# 1x9x1_3.net
KiCad netlist of a schematic drawn in Altium Designer
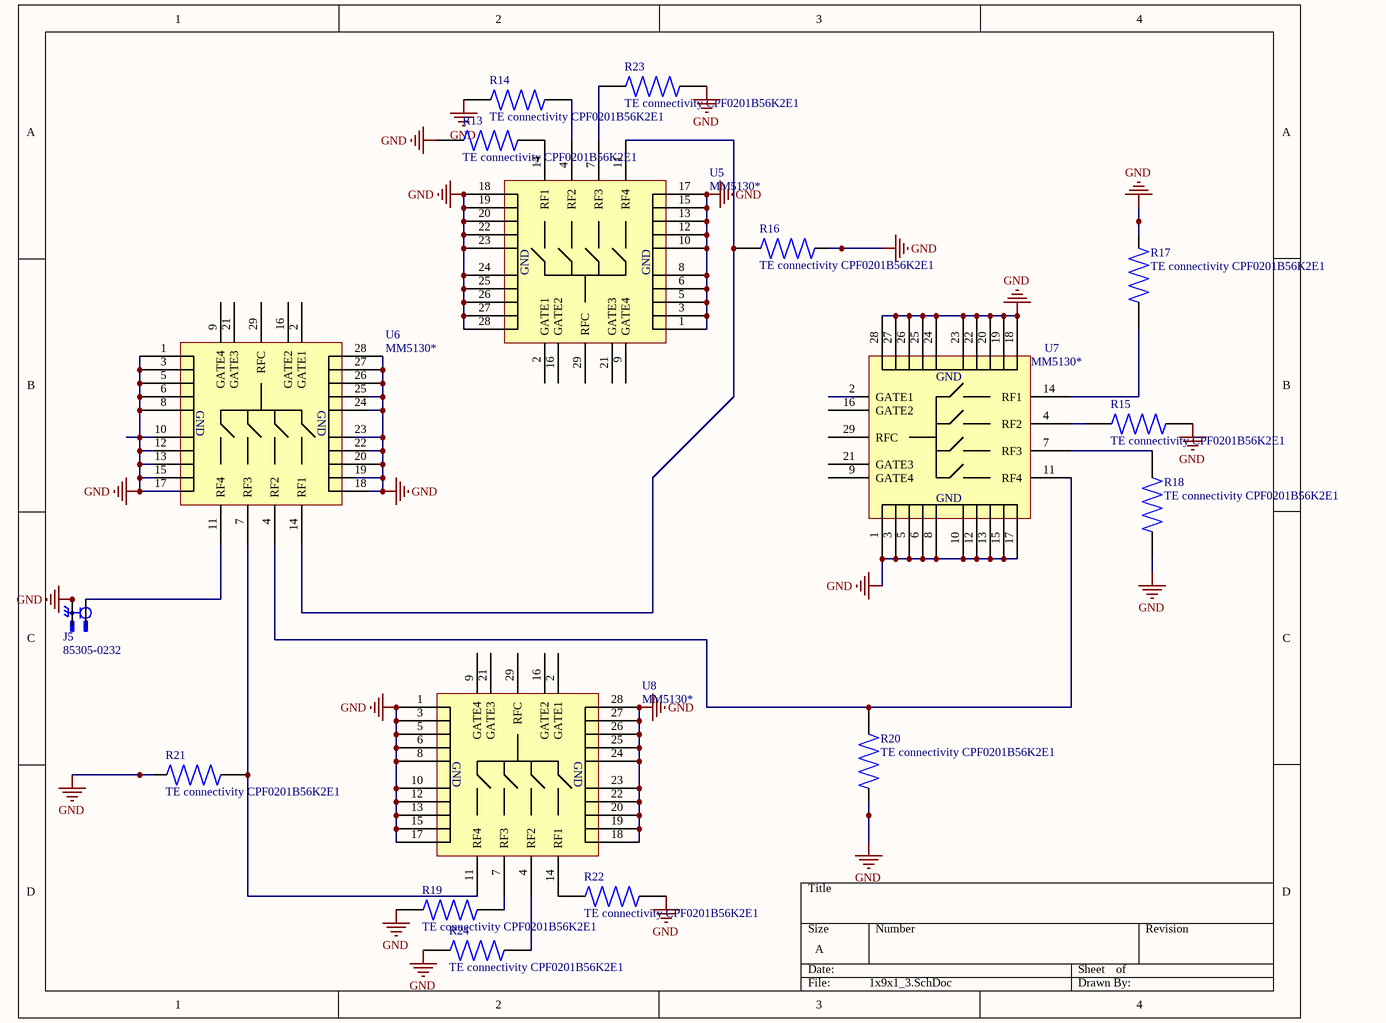
[diagram p0: 1x9x1_3.SchDoc]

(export (version "E")
  (design (tool "Eeschema 10.0.6"))
  (components
    (comp (ref "J5")
      (value "85305-0232")
      (footprint "MOLEX_85305-0232")
      (description "SMP Connector Plug, Male Pin 50Ohm Surface Mount Solder")
      (fields (field (name "MP") "853050232") (field (name "MF") "Molex"))
      (libsource (lib "85305-0232") (part "85305-0232"))
    )
    (comp (ref "R13")
      (value "TE connectivity CPF0201B56K2E1")
      (footprint "0201-resistor")
      (description "CPF 0201 56K2 0.1% 25PPM 1K RL")
      (fields (field (name "MP") "ERJ1GN0R00C") (field (name "MFGR PART NO.") "CPF0201B56K2E1"))
      (libsource (lib "SchlibLafe") (part "TE connectivity CPF0201B56K2E1"))
    )
    (comp (ref "R14")
      (value "TE connectivity CPF0201B56K2E1")
      (footprint "0201-resistor")
      (description "CPF 0201 56K2 0.1% 25PPM 1K RL")
      (fields (field (name "MP") "ERJ1GN0R00C") (field (name "MFGR PART NO.") "CPF0201B56K2E1"))
      (libsource (lib "SchlibLafe") (part "TE connectivity CPF0201B56K2E1"))
    )
    (comp (ref "R15")
      (value "TE connectivity CPF0201B56K2E1")
      (footprint "0201-resistor")
      (description "CPF 0201 56K2 0.1% 25PPM 1K RL")
      (fields (field (name "MP") "ERJ1GN0R00C") (field (name "MFGR PART NO.") "CPF0201B56K2E1"))
      (libsource (lib "SchlibLafe") (part "TE connectivity CPF0201B56K2E1"))
    )
    (comp (ref "R16")
      (value "TE connectivity CPF0201B56K2E1")
      (footprint "0201-resistor")
      (description "CPF 0201 56K2 0.1% 25PPM 1K RL")
      (fields (field (name "MP") "ERJ1GN0R00C") (field (name "MFGR PART NO.") "CPF0201B56K2E1"))
      (libsource (lib "SchlibLafe") (part "TE connectivity CPF0201B56K2E1"))
    )
    (comp (ref "R17")
      (value "TE connectivity CPF0201B56K2E1")
      (footprint "0201-resistor")
      (description "CPF 0201 56K2 0.1% 25PPM 1K RL")
      (fields (field (name "MP") "ERJ1GN0R00C") (field (name "MFGR PART NO.") "CPF0201B56K2E1"))
      (libsource (lib "SchlibLafe") (part "TE connectivity CPF0201B56K2E1"))
    )
    (comp (ref "R18")
      (value "TE connectivity CPF0201B56K2E1")
      (footprint "0201-resistor")
      (description "CPF 0201 56K2 0.1% 25PPM 1K RL")
      (fields (field (name "MP") "ERJ1GN0R00C") (field (name "MFGR PART NO.") "CPF0201B56K2E1"))
      (libsource (lib "SchlibLafe") (part "TE connectivity CPF0201B56K2E1"))
    )
    (comp (ref "R19")
      (value "TE connectivity CPF0201B56K2E1")
      (footprint "0201-resistor")
      (description "CPF 0201 56K2 0.1% 25PPM 1K RL")
      (fields (field (name "MP") "ERJ1GN0R00C") (field (name "MFGR PART NO.") "CPF0201B56K2E1"))
      (libsource (lib "SchlibLafe") (part "TE connectivity CPF0201B56K2E1"))
    )
    (comp (ref "R20")
      (value "TE connectivity CPF0201B56K2E1")
      (footprint "0201-resistor")
      (description "CPF 0201 56K2 0.1% 25PPM 1K RL")
      (fields (field (name "MP") "ERJ1GN0R00C") (field (name "MFGR PART NO.") "CPF0201B56K2E1"))
      (libsource (lib "SchlibLafe") (part "TE connectivity CPF0201B56K2E1"))
    )
    (comp (ref "R21")
      (value "TE connectivity CPF0201B56K2E1")
      (footprint "0201-resistor")
      (description "CPF 0201 56K2 0.1% 25PPM 1K RL")
      (fields (field (name "MP") "ERJ1GN0R00C") (field (name "MFGR PART NO.") "CPF0201B56K2E1"))
      (libsource (lib "SchlibLafe") (part "TE connectivity CPF0201B56K2E1"))
    )
    (comp (ref "R22")
      (value "TE connectivity CPF0201B56K2E1")
      (footprint "0201-resistor")
      (description "CPF 0201 56K2 0.1% 25PPM 1K RL")
      (fields (field (name "MP") "ERJ1GN0R00C") (field (name "MFGR PART NO.") "CPF0201B56K2E1"))
      (libsource (lib "SchlibLafe") (part "TE connectivity CPF0201B56K2E1"))
    )
    (comp (ref "R23")
      (value "TE connectivity CPF0201B56K2E1")
      (footprint "0201-resistor")
      (description "CPF 0201 56K2 0.1% 25PPM 1K RL")
      (fields (field (name "MP") "ERJ1GN0R00C") (field (name "MFGR PART NO.") "CPF0201B56K2E1"))
      (libsource (lib "SchlibLafe") (part "TE connectivity CPF0201B56K2E1"))
    )
    (comp (ref "R24")
      (value "TE connectivity CPF0201B56K2E1")
      (footprint "0201-resistor")
      (description "CPF 0201 56K2 0.1% 25PPM 1K RL")
      (fields (field (name "MP") "ERJ1GN0R00C") (field (name "MFGR PART NO.") "CPF0201B56K2E1"))
      (libsource (lib "SchlibLafe") (part "TE connectivity CPF0201B56K2E1"))
    )
    (comp (ref "U5")
      (value "MM5130*")
      (footprint "MM5130-NORM_PCB_NOFLOOD")
      (description "High power SP4T MEMs switch")
      (libsource (lib "MM5130_SCHSYM") (part "IC-MM5130"))
    )
    (comp (ref "U6")
      (value "MM5130*")
      (footprint "MM5130-NORM_PCB_NOFLOOD")
      (description "High power SP4T MEMs switch")
      (libsource (lib "") (part "IC-MM5130_1"))
    )
    (comp (ref "U7")
      (value "MM5130*")
      (footprint "MM5130-NORM_PCB_NOFLOOD")
      (description "High power SP4T MEMs switch")
      (libsource (lib "") (part "IC-MM5130_2"))
    )
    (comp (ref "U8")
      (value "MM5130*")
      (footprint "MM5130-NORM_PCB_NOFLOOD")
      (description "High power SP4T MEMs switch")
      (libsource (lib "") (part "IC-MM5130_1"))
    )
  )
  (nets
    (net (code "1") (name "GND") (class "Default")
      (node (ref "J5") (pin "10") (pinfunction "2_10") (pintype "passive"))
      (node (ref "J5") (pin "11") (pinfunction "2_11") (pintype "passive"))
      (node (ref "J5") (pin "12") (pinfunction "2_12") (pintype "passive"))
      (node (ref "J5") (pin "13") (pinfunction "2_13") (pintype "passive"))
      (node (ref "J5") (pin "14") (pinfunction "2_14") (pintype "passive"))
      (node (ref "J5") (pin "15") (pinfunction "2_15") (pintype "passive"))
      (node (ref "J5") (pin "16") (pinfunction "2_16") (pintype "passive"))
      (node (ref "J5") (pin "17") (pinfunction "2_17") (pintype "passive"))
      (node (ref "J5") (pin "18") (pinfunction "2_18") (pintype "passive"))
      (node (ref "J5") (pin "2") (pinfunction "2_2") (pintype "passive"))
      (node (ref "J5") (pin "3") (pinfunction "2_3") (pintype "passive"))
      (node (ref "J5") (pin "4") (pinfunction "2_4") (pintype "passive"))
      (node (ref "J5") (pin "5") (pinfunction "2_5") (pintype "passive"))
      (node (ref "J5") (pin "6") (pinfunction "2_6") (pintype "passive"))
      (node (ref "J5") (pin "7") (pinfunction "2_7") (pintype "passive"))
      (node (ref "J5") (pin "8") (pinfunction "2_8") (pintype "passive"))
      (node (ref "J5") (pin "9") (pinfunction "2_9") (pintype "passive"))
      (node (ref "R13") (pin "1") (pinfunction "1_1") (pintype "passive"))
      (node (ref "R14") (pin "2") (pinfunction "2_2") (pintype "passive"))
      (node (ref "R15") (pin "2") (pinfunction "2_2") (pintype "passive"))
      (node (ref "R16") (pin "1") (pinfunction "1_1") (pintype "passive"))
      (node (ref "R17") (pin "1") (pinfunction "1_1") (pintype "passive"))
      (node (ref "R18") (pin "1") (pinfunction "1_1") (pintype "passive"))
      (node (ref "R19") (pin "1") (pinfunction "1_1") (pintype "passive"))
      (node (ref "R20") (pin "2") (pinfunction "2_2") (pintype "passive"))
      (node (ref "R21") (pin "2") (pinfunction "2_2") (pintype "passive"))
      (node (ref "R22") (pin "1") (pinfunction "1_1") (pintype "passive"))
      (node (ref "R23") (pin "1") (pinfunction "1_1") (pintype "passive"))
      (node (ref "R24") (pin "1") (pinfunction "1_1") (pintype "passive"))
      (node (ref "U5") (pin "1") (pinfunction "GND_1") (pintype "passive"))
      (node (ref "U5") (pin "10") (pinfunction "GND_10") (pintype "passive"))
      (node (ref "U5") (pin "12") (pinfunction "GND_12") (pintype "passive"))
      (node (ref "U5") (pin "13") (pinfunction "GND_13") (pintype "passive"))
      (node (ref "U5") (pin "15") (pinfunction "GND_15") (pintype "passive"))
      (node (ref "U5") (pin "17") (pinfunction "GND_17") (pintype "passive"))
      (node (ref "U5") (pin "18") (pinfunction "GND_18") (pintype "passive"))
      (node (ref "U5") (pin "19") (pinfunction "GND_19") (pintype "passive"))
      (node (ref "U5") (pin "20") (pinfunction "GND_20") (pintype "passive"))
      (node (ref "U5") (pin "22") (pinfunction "GND_22") (pintype "passive"))
      (node (ref "U5") (pin "23") (pinfunction "GND_23") (pintype "passive"))
      (node (ref "U5") (pin "24") (pinfunction "GND_24") (pintype "passive"))
      (node (ref "U5") (pin "25") (pinfunction "GND_25") (pintype "passive"))
      (node (ref "U5") (pin "26") (pinfunction "GND_26") (pintype "passive"))
      (node (ref "U5") (pin "27") (pinfunction "GND_27") (pintype "passive"))
      (node (ref "U5") (pin "28") (pinfunction "GND_28") (pintype "passive"))
      (node (ref "U5") (pin "3") (pinfunction "GND_3") (pintype "passive"))
      (node (ref "U5") (pin "5") (pinfunction "GND_5") (pintype "passive"))
      (node (ref "U5") (pin "6") (pinfunction "GND_6") (pintype "passive"))
      (node (ref "U5") (pin "8") (pinfunction "GND_8") (pintype "passive"))
      (node (ref "U6") (pin "1") (pinfunction "GND_1") (pintype "passive"))
      (node (ref "U6") (pin "10") (pinfunction "GND_10") (pintype "passive"))
      (node (ref "U6") (pin "12") (pinfunction "GND_12") (pintype "passive"))
      (node (ref "U6") (pin "13") (pinfunction "GND_13") (pintype "passive"))
      (node (ref "U6") (pin "15") (pinfunction "GND_15") (pintype "passive"))
      (node (ref "U6") (pin "17") (pinfunction "GND_17") (pintype "passive"))
      (node (ref "U6") (pin "18") (pinfunction "GND_18") (pintype "passive"))
      (node (ref "U6") (pin "19") (pinfunction "GND_19") (pintype "passive"))
      (node (ref "U6") (pin "20") (pinfunction "GND_20") (pintype "passive"))
      (node (ref "U6") (pin "22") (pinfunction "GND_22") (pintype "passive"))
      (node (ref "U6") (pin "23") (pinfunction "GND_23") (pintype "passive"))
      (node (ref "U6") (pin "24") (pinfunction "GND_24") (pintype "passive"))
      (node (ref "U6") (pin "25") (pinfunction "GND_25") (pintype "passive"))
      (node (ref "U6") (pin "26") (pinfunction "GND_26") (pintype "passive"))
      (node (ref "U6") (pin "27") (pinfunction "GND_27") (pintype "passive"))
      (node (ref "U6") (pin "28") (pinfunction "GND_28") (pintype "passive"))
      (node (ref "U6") (pin "3") (pinfunction "GND_3") (pintype "passive"))
      (node (ref "U6") (pin "5") (pinfunction "GND_5") (pintype "passive"))
      (node (ref "U6") (pin "6") (pinfunction "GND_6") (pintype "passive"))
      (node (ref "U6") (pin "8") (pinfunction "GND_8") (pintype "passive"))
      (node (ref "U7") (pin "1") (pinfunction "GND_1") (pintype "passive"))
      (node (ref "U7") (pin "10") (pinfunction "GND_10") (pintype "passive"))
      (node (ref "U7") (pin "12") (pinfunction "GND_12") (pintype "passive"))
      (node (ref "U7") (pin "13") (pinfunction "GND_13") (pintype "passive"))
      (node (ref "U7") (pin "15") (pinfunction "GND_15") (pintype "passive"))
      (node (ref "U7") (pin "17") (pinfunction "GND_17") (pintype "passive"))
      (node (ref "U7") (pin "18") (pinfunction "GND_18") (pintype "passive"))
      (node (ref "U7") (pin "19") (pinfunction "GND_19") (pintype "passive"))
      (node (ref "U7") (pin "20") (pinfunction "GND_20") (pintype "passive"))
      (node (ref "U7") (pin "22") (pinfunction "GND_22") (pintype "passive"))
      (node (ref "U7") (pin "23") (pinfunction "GND_23") (pintype "passive"))
      (node (ref "U7") (pin "24") (pinfunction "GND_24") (pintype "passive"))
      (node (ref "U7") (pin "25") (pinfunction "GND_25") (pintype "passive"))
      (node (ref "U7") (pin "26") (pinfunction "GND_26") (pintype "passive"))
      (node (ref "U7") (pin "27") (pinfunction "GND_27") (pintype "passive"))
      (node (ref "U7") (pin "28") (pinfunction "GND_28") (pintype "passive"))
      (node (ref "U7") (pin "3") (pinfunction "GND_3") (pintype "passive"))
      (node (ref "U7") (pin "5") (pinfunction "GND_5") (pintype "passive"))
      (node (ref "U7") (pin "6") (pinfunction "GND_6") (pintype "passive"))
      (node (ref "U7") (pin "8") (pinfunction "GND_8") (pintype "passive"))
      (node (ref "U8") (pin "1") (pinfunction "GND_1") (pintype "passive"))
      (node (ref "U8") (pin "10") (pinfunction "GND_10") (pintype "passive"))
      (node (ref "U8") (pin "12") (pinfunction "GND_12") (pintype "passive"))
      (node (ref "U8") (pin "13") (pinfunction "GND_13") (pintype "passive"))
      (node (ref "U8") (pin "15") (pinfunction "GND_15") (pintype "passive"))
      (node (ref "U8") (pin "17") (pinfunction "GND_17") (pintype "passive"))
      (node (ref "U8") (pin "18") (pinfunction "GND_18") (pintype "passive"))
      (node (ref "U8") (pin "19") (pinfunction "GND_19") (pintype "passive"))
      (node (ref "U8") (pin "20") (pinfunction "GND_20") (pintype "passive"))
      (node (ref "U8") (pin "22") (pinfunction "GND_22") (pintype "passive"))
      (node (ref "U8") (pin "23") (pinfunction "GND_23") (pintype "passive"))
      (node (ref "U8") (pin "24") (pinfunction "GND_24") (pintype "passive"))
      (node (ref "U8") (pin "25") (pinfunction "GND_25") (pintype "passive"))
      (node (ref "U8") (pin "26") (pinfunction "GND_26") (pintype "passive"))
      (node (ref "U8") (pin "27") (pinfunction "GND_27") (pintype "passive"))
      (node (ref "U8") (pin "28") (pinfunction "GND_28") (pintype "passive"))
      (node (ref "U8") (pin "3") (pinfunction "GND_3") (pintype "passive"))
      (node (ref "U8") (pin "5") (pinfunction "GND_5") (pintype "passive"))
      (node (ref "U8") (pin "6") (pinfunction "GND_6") (pintype "passive"))
      (node (ref "U8") (pin "8") (pinfunction "GND_8") (pintype "passive"))
    )
    (net (code "2") (name "Net-(U5-RF1)") (class "Default")
      (node (ref "R13") (pin "2") (pinfunction "2_2") (pintype "passive"))
      (node (ref "U5") (pin "14") (pinfunction "RF1_14") (pintype "passive"))
    )
    (net (code "3") (name "Net-(U5-RF2)") (class "Default")
      (node (ref "R14") (pin "1") (pinfunction "1_1") (pintype "passive"))
      (node (ref "U5") (pin "4") (pinfunction "RF2_4") (pintype "passive"))
    )
    (net (code "4") (name "Net-(U5-RF3)") (class "Default")
      (node (ref "R23") (pin "2") (pinfunction "2_2") (pintype "passive"))
      (node (ref "U5") (pin "7") (pinfunction "RF3_7") (pintype "passive"))
    )
    (net (code "5") (name "Net-(U5-RF4)") (class "Default")
      (node (ref "R16") (pin "2") (pinfunction "2_2") (pintype "passive"))
      (node (ref "U5") (pin "11") (pinfunction "RF4_11") (pintype "passive"))
      (node (ref "U6") (pin "14") (pinfunction "RF1_14") (pintype "passive"))
    )
    (net (code "6") (name "Net-(U6-RF2)") (class "Default")
      (node (ref "R20") (pin "1") (pinfunction "1_1") (pintype "passive"))
      (node (ref "U6") (pin "4") (pinfunction "RF2_4") (pintype "passive"))
      (node (ref "U7") (pin "11") (pinfunction "RF4_11") (pintype "passive"))
    )
    (net (code "7") (name "Net-(U6-RF3)") (class "Default")
      (node (ref "R21") (pin "1") (pinfunction "1_1") (pintype "passive"))
      (node (ref "U6") (pin "7") (pinfunction "RF3_7") (pintype "passive"))
      (node (ref "U8") (pin "11") (pinfunction "RF4_11") (pintype "passive"))
    )
    (net (code "8") (name "Net-(U6-RF4)") (class "Default")
      (node (ref "J5") (pin "1") (pinfunction "1_1") (pintype "passive"))
      (node (ref "U6") (pin "11") (pinfunction "RF4_11") (pintype "passive"))
    )
    (net (code "9") (name "Net-(U7-RF1)") (class "Default")
      (node (ref "R17") (pin "2") (pinfunction "2_2") (pintype "passive"))
      (node (ref "U7") (pin "14") (pinfunction "RF1_14") (pintype "passive"))
    )
    (net (code "10") (name "Net-(U7-RF2)") (class "Default")
      (node (ref "R15") (pin "1") (pinfunction "1_1") (pintype "passive"))
      (node (ref "U7") (pin "4") (pinfunction "RF2_4") (pintype "passive"))
    )
    (net (code "11") (name "Net-(U7-RF3)") (class "Default")
      (node (ref "R18") (pin "2") (pinfunction "2_2") (pintype "passive"))
      (node (ref "U7") (pin "7") (pinfunction "RF3_7") (pintype "passive"))
    )
    (net (code "12") (name "Net-(U8-RF1)") (class "Default")
      (node (ref "R22") (pin "2") (pinfunction "2_2") (pintype "passive"))
      (node (ref "U8") (pin "14") (pinfunction "RF1_14") (pintype "passive"))
    )
    (net (code "13") (name "Net-(U8-RF2)") (class "Default")
      (node (ref "R24") (pin "2") (pinfunction "2_2") (pintype "passive"))
      (node (ref "U8") (pin "4") (pinfunction "RF2_4") (pintype "passive"))
    )
    (net (code "14") (name "Net-(U8-RF3)") (class "Default")
      (node (ref "R19") (pin "2") (pinfunction "2_2") (pintype "passive"))
      (node (ref "U8") (pin "7") (pinfunction "RF3_7") (pintype "passive"))
    )
    (net (code "15") (name "unconnected-(U5-GATE1-Pad2)") (class "Default")
      (node (ref "U5") (pin "2") (pinfunction "GATE1_2") (pintype "passive"))
    )
    (net (code "16") (name "unconnected-(U5-GATE2-Pad16)") (class "Default")
      (node (ref "U5") (pin "16") (pinfunction "GATE2_16") (pintype "passive"))
    )
    (net (code "17") (name "unconnected-(U5-GATE3-Pad21)") (class "Default")
      (node (ref "U5") (pin "21") (pinfunction "GATE3_21") (pintype "passive"))
    )
    (net (code "18") (name "unconnected-(U5-GATE4-Pad9)") (class "Default")
      (node (ref "U5") (pin "9") (pinfunction "GATE4_9") (pintype "passive"))
    )
    (net (code "19") (name "unconnected-(U5-RFC-Pad29)") (class "Default")
      (node (ref "U5") (pin "29") (pinfunction "RFC_29") (pintype "passive"))
    )
    (net (code "20") (name "unconnected-(U6-GATE1-Pad2)") (class "Default")
      (node (ref "U6") (pin "2") (pinfunction "GATE1_2") (pintype "passive"))
    )
    (net (code "21") (name "unconnected-(U6-GATE2-Pad16)") (class "Default")
      (node (ref "U6") (pin "16") (pinfunction "GATE2_16") (pintype "passive"))
    )
    (net (code "22") (name "unconnected-(U6-GATE3-Pad21)") (class "Default")
      (node (ref "U6") (pin "21") (pinfunction "GATE3_21") (pintype "passive"))
    )
    (net (code "23") (name "unconnected-(U6-GATE4-Pad9)") (class "Default")
      (node (ref "U6") (pin "9") (pinfunction "GATE4_9") (pintype "passive"))
    )
    (net (code "24") (name "unconnected-(U6-RFC-Pad29)") (class "Default")
      (node (ref "U6") (pin "29") (pinfunction "RFC_29") (pintype "passive"))
    )
    (net (code "25") (name "unconnected-(U7-GATE1-Pad2)") (class "Default")
      (node (ref "U7") (pin "2") (pinfunction "GATE1_2") (pintype "passive"))
    )
    (net (code "26") (name "unconnected-(U7-GATE2-Pad16)") (class "Default")
      (node (ref "U7") (pin "16") (pinfunction "GATE2_16") (pintype "passive"))
    )
    (net (code "27") (name "unconnected-(U7-GATE3-Pad21)") (class "Default")
      (node (ref "U7") (pin "21") (pinfunction "GATE3_21") (pintype "passive"))
    )
    (net (code "28") (name "unconnected-(U7-GATE4-Pad9)") (class "Default")
      (node (ref "U7") (pin "9") (pinfunction "GATE4_9") (pintype "passive"))
    )
    (net (code "29") (name "unconnected-(U7-RFC-Pad29)") (class "Default")
      (node (ref "U7") (pin "29") (pinfunction "RFC_29") (pintype "passive"))
    )
    (net (code "30") (name "unconnected-(U8-GATE1-Pad2)") (class "Default")
      (node (ref "U8") (pin "2") (pinfunction "GATE1_2") (pintype "passive"))
    )
    (net (code "31") (name "unconnected-(U8-GATE2-Pad16)") (class "Default")
      (node (ref "U8") (pin "16") (pinfunction "GATE2_16") (pintype "passive"))
    )
    (net (code "32") (name "unconnected-(U8-GATE3-Pad21)") (class "Default")
      (node (ref "U8") (pin "21") (pinfunction "GATE3_21") (pintype "passive"))
    )
    (net (code "33") (name "unconnected-(U8-GATE4-Pad9)") (class "Default")
      (node (ref "U8") (pin "9") (pinfunction "GATE4_9") (pintype "passive"))
    )
    (net (code "34") (name "unconnected-(U8-RFC-Pad29)") (class "Default")
      (node (ref "U8") (pin "29") (pinfunction "RFC_29") (pintype "passive"))
    )
  )
)
